# Steckkarte.net
KiCad netlist of a schematic drawn in EAGLE
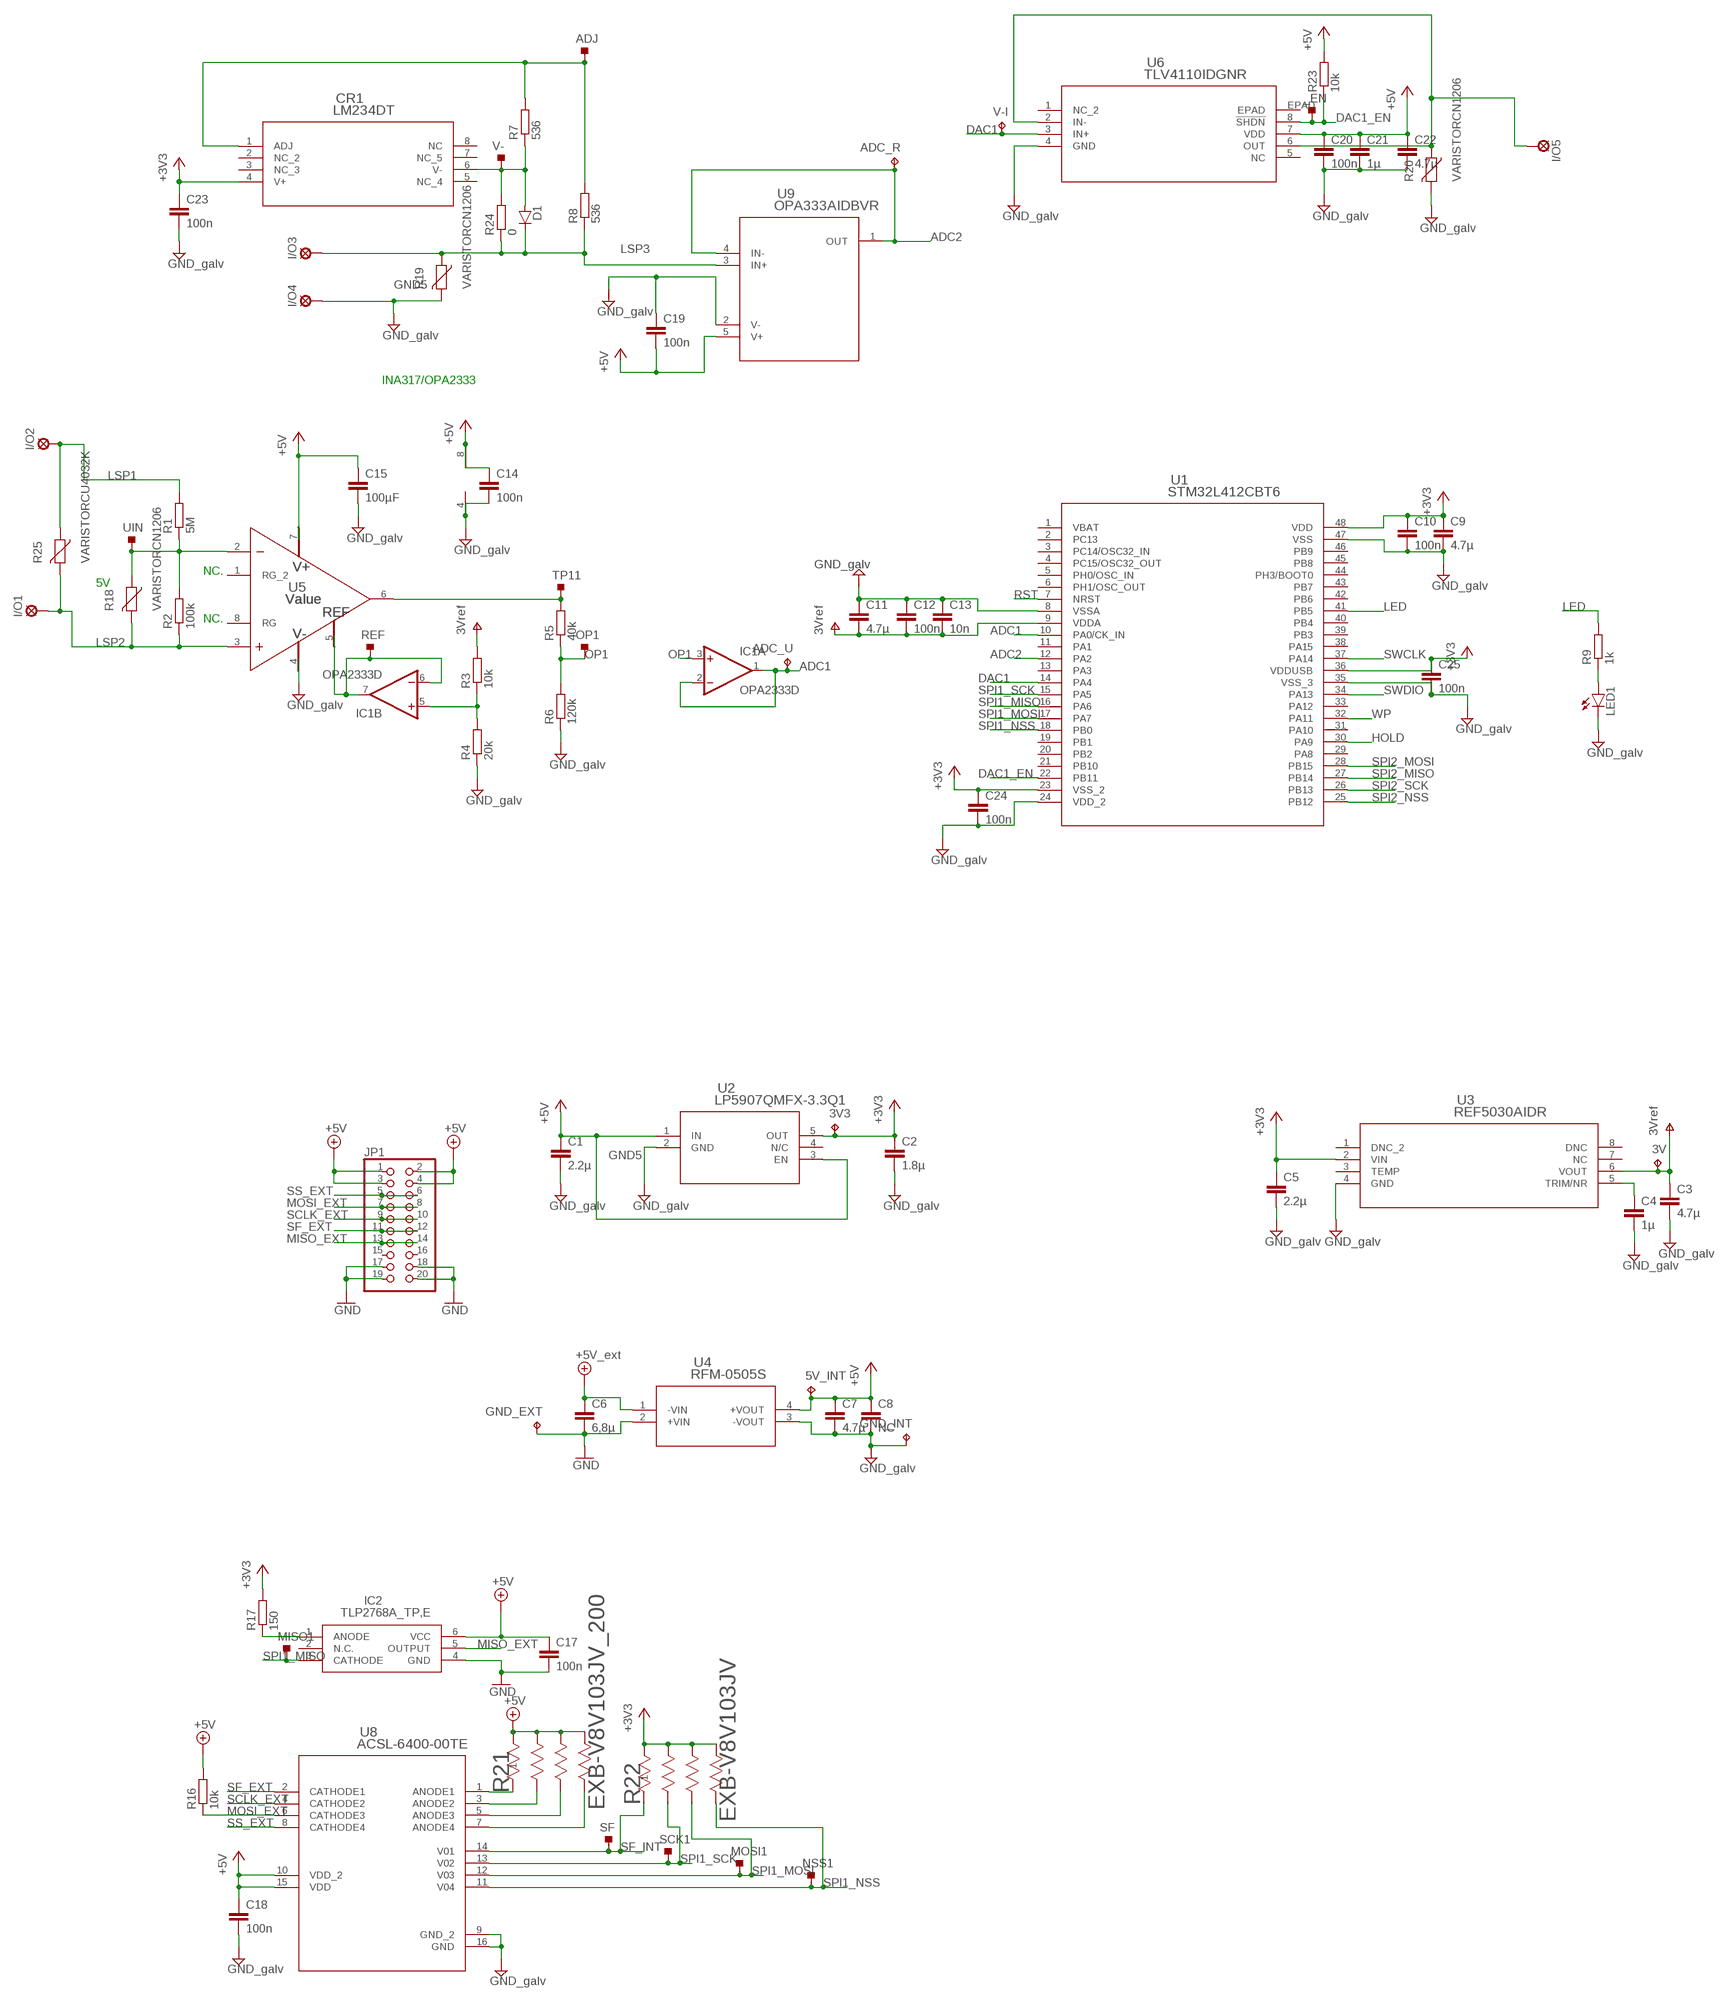
[diagram p0: schematic, sheet 1, part 1 of 2]
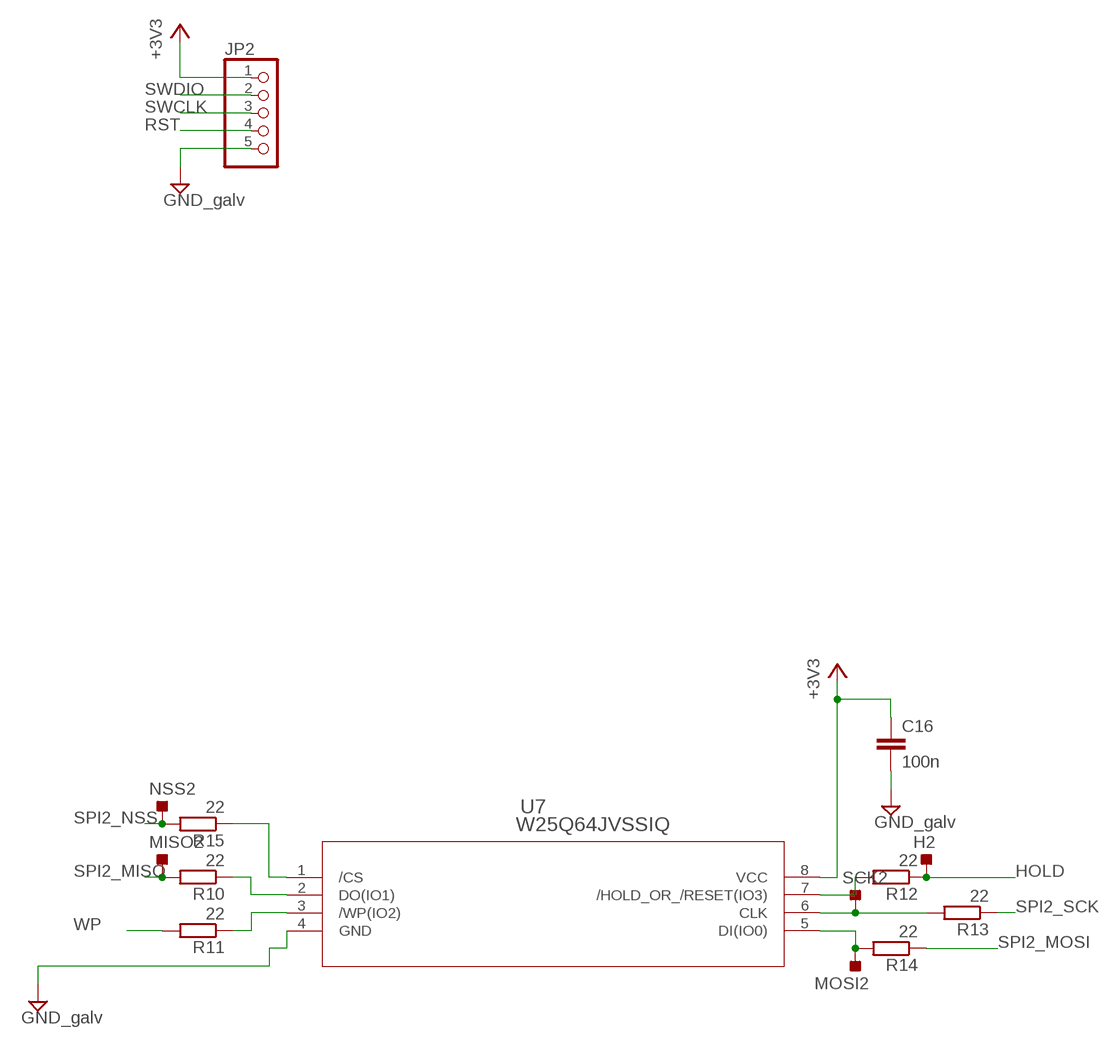
[diagram p1: schematic, sheet 1, part 2 of 2]

(export (version "E")
  (design (tool "Eeschema 10.0.6"))
  (components
    (comp (ref "3V")
      (value "TPPAD1-13")
      (footprint "eagle-import:P1-13")
      (libsource (lib "eagle-import") (part "TPPAD1-13"))
    )
    (comp (ref "3V3")
      (value "TPPAD1-13")
      (footprint "eagle-import:P1-13")
      (libsource (lib "eagle-import") (part "TPPAD1-13"))
    )
    (comp (ref "5V_INT")
      (value "TPPAD1-13")
      (footprint "eagle-import:P1-13")
      (libsource (lib "eagle-import") (part "TPPAD1-13"))
    )
    (comp (ref "ADC_R")
      (value "TPPAD1-13")
      (footprint "eagle-import:P1-13")
      (libsource (lib "eagle-import") (part "TPPAD1-13"))
    )
    (comp (ref "ADC_U")
      (value "TPPAD1-13")
      (footprint "eagle-import:P1-13")
      (libsource (lib "eagle-import") (part "TPPAD1-13"))
    )
    (comp (ref "ADJ")
      (value "TESTPOINT_TPS-SMD-10SN")
      (footprint "eagle-import:TESTPOINT_SMD-10SN")
      (libsource (lib "eagle-import") (part "TESTPOINT_TPS-SMD-10SN"))
    )
    (comp (ref "C1")
      (value "2.2µ")
      (footprint "eagle-import:C0603K")
      (libsource (lib "eagle-import") (part "C-EUC0603K"))
    )
    (comp (ref "C2")
      (value "1.8µ")
      (footprint "eagle-import:C1206K")
      (libsource (lib "eagle-import") (part "C-EUC1206K"))
    )
    (comp (ref "C3")
      (value "4.7µ")
      (footprint "eagle-import:C0603K")
      (libsource (lib "eagle-import") (part "C-EUC0603K"))
    )
    (comp (ref "C4")
      (value "1µ")
      (footprint "eagle-import:C0603K")
      (libsource (lib "eagle-import") (part "C-EUC0603K"))
    )
    (comp (ref "C5")
      (value "2.2µ")
      (footprint "eagle-import:C0603K")
      (libsource (lib "eagle-import") (part "C-EUC0603K"))
    )
    (comp (ref "C6")
      (value "6,8µ")
      (footprint "eagle-import:C0603K")
      (libsource (lib "eagle-import") (part "resistor_348_C-EUC0603K"))
    )
    (comp (ref "C7")
      (value "4.7µ")
      (footprint "eagle-import:C0603K")
      (libsource (lib "eagle-import") (part "resistor_348_C-EUC0603K"))
    )
    (comp (ref "C8")
      (value "NC")
      (footprint "eagle-import:C0603K")
      (libsource (lib "eagle-import") (part "resistor_348_C-EUC0603K"))
    )
    (comp (ref "C9")
      (value "4.7µ")
      (footprint "eagle-import:C0603K")
      (libsource (lib "eagle-import") (part "C-EUC0603K"))
    )
    (comp (ref "C10")
      (value "100n")
      (footprint "eagle-import:C0603K")
      (libsource (lib "eagle-import") (part "C-EUC0603K"))
    )
    (comp (ref "C11")
      (value "4.7µ")
      (footprint "eagle-import:C0603K")
      (libsource (lib "eagle-import") (part "C-EUC0603K"))
    )
    (comp (ref "C12")
      (value "100n")
      (footprint "eagle-import:C0603K")
      (libsource (lib "eagle-import") (part "C-EUC0603K"))
    )
    (comp (ref "C13")
      (value "10n")
      (footprint "eagle-import:C0603K")
      (libsource (lib "eagle-import") (part "C-EUC0603K"))
    )
    (comp (ref "C14")
      (value "100n")
      (footprint "eagle-import:C0603K")
      (libsource (lib "eagle-import") (part "C-EUC0603K"))
    )
    (comp (ref "C15")
      (value "100µF")
      (footprint "eagle-import:C1206K")
      (libsource (lib "eagle-import") (part "resistor_348_C-EUC1206K"))
    )
    (comp (ref "C16")
      (value "100n")
      (footprint "eagle-import:C0603K")
      (libsource (lib "eagle-import") (part "C-EUC0603K"))
    )
    (comp (ref "C17")
      (value "100n")
      (footprint "eagle-import:C0603K")
      (libsource (lib "eagle-import") (part "C-EUC0603K"))
    )
    (comp (ref "C18")
      (value "100n")
      (footprint "eagle-import:C0603K")
      (libsource (lib "eagle-import") (part "C-EUC0603K"))
    )
    (comp (ref "C19")
      (value "100n")
      (footprint "eagle-import:C0603K")
      (libsource (lib "eagle-import") (part "C-EUC0603K"))
    )
    (comp (ref "C20")
      (value "100n")
      (footprint "eagle-import:C0603K")
      (libsource (lib "eagle-import") (part "C-EUC0603K"))
    )
    (comp (ref "C21")
      (value "1µ")
      (footprint "eagle-import:C0603K")
      (libsource (lib "eagle-import") (part "C-EUC0603K"))
    )
    (comp (ref "C22")
      (value "4.7µ")
      (footprint "eagle-import:C0603K")
      (libsource (lib "eagle-import") (part "C-EUC0603K"))
    )
    (comp (ref "C23")
      (value "100n")
      (footprint "eagle-import:C0603K")
      (libsource (lib "eagle-import") (part "C-EUC0603K"))
    )
    (comp (ref "C24")
      (value "100n")
      (footprint "eagle-import:C0603K")
      (libsource (lib "eagle-import") (part "C-EUC0603K"))
    )
    (comp (ref "C25")
      (value "100n")
      (footprint "eagle-import:C0603K")
      (libsource (lib "eagle-import") (part "C-EUC0603K"))
    )
    (comp (ref "CR1")
      (value "LM234DT")
      (footprint "eagle-import:SO-8")
      (libsource (lib "eagle-import") (part "LM234DT"))
    )
    (comp (ref "D1")
      (value "D-SOD123")
      (footprint "eagle-import:SOD123")
      (libsource (lib "eagle-import") (part "D-SOD123"))
    )
    (comp (ref "GND_EXT")
      (value "TPPAD1-13")
      (footprint "eagle-import:P1-13")
      (libsource (lib "eagle-import") (part "TPPAD1-13"))
    )
    (comp (ref "GND_INT")
      (value "TPPAD1-13")
      (footprint "eagle-import:P1-13")
      (libsource (lib "eagle-import") (part "TPPAD1-13"))
    )
    (comp (ref "H2")
      (value "TESTPOINT_TPS-SMD-10SN")
      (footprint "eagle-import:TESTPOINT_SMD-10SN")
      (libsource (lib "eagle-import") (part "TESTPOINT_TPS-SMD-10SN"))
    )
    (comp (ref "I/O1")
      (value "SE14")
      (footprint "eagle-import:SE14")
      (libsource (lib "eagle-import") (part "SE14"))
    )
    (comp (ref "I/O2")
      (value "SE14")
      (footprint "eagle-import:SE14")
      (libsource (lib "eagle-import") (part "SE14"))
    )
    (comp (ref "I/O3")
      (value "SE14")
      (footprint "eagle-import:SE14")
      (libsource (lib "eagle-import") (part "SE14"))
    )
    (comp (ref "I/O4")
      (value "SE14")
      (footprint "eagle-import:SE14")
      (libsource (lib "eagle-import") (part "SE14"))
    )
    (comp (ref "I/O5")
      (value "SE14")
      (footprint "eagle-import:SE14")
      (libsource (lib "eagle-import") (part "SE14"))
    )
    (comp (ref "IC1")
      (value "OPA2333D")
      (footprint "eagle-import:SO08")
      (libsource (lib "eagle-import") (part "OPA2333D"))
    )
    (comp (ref "IC2")
      (value "TLP2768A_TP,E")
      (footprint "eagle-import:SOIC127P1000X220-6N")
      (fields
        (field (name "MANUFACTURER_PART_NUMBER") "TLP2768A(TP,E")
        (field (name "MOUSER_PART_NUMBER") "757-TLP2768ATPE")
      )
      (libsource (lib "eagle-import") (part "TLP2768A_TP,E"))
    )
    (comp (ref "JP1")
      (value "PINHD-2X10/90")
      (footprint "eagle-import:2X10_90")
      (libsource (lib "eagle-import") (part "PINHD-2X10/90"))
    )
    (comp (ref "JP2")
      (value "PINHD-1X5")
      (footprint "eagle-import:1X05")
      (libsource (lib "eagle-import") (part "PINHD-1X5"))
    )
    (comp (ref "LED1")
      (value "LED5MM")
      (footprint "eagle-import:LED5MM")
      (libsource (lib "eagle-import") (part "LED5MM"))
    )
    (comp (ref "MISO1")
      (value "TESTPOINT_TPS-SMD-10SN")
      (footprint "eagle-import:TESTPOINT_SMD-10SN")
      (libsource (lib "eagle-import") (part "TESTPOINT_TPS-SMD-10SN"))
    )
    (comp (ref "MISO2")
      (value "TESTPOINT_TPS-SMD-10SN")
      (footprint "eagle-import:TESTPOINT_SMD-10SN")
      (libsource (lib "eagle-import") (part "TESTPOINT_TPS-SMD-10SN"))
    )
    (comp (ref "MOSI1")
      (value "TESTPOINT_TPS-SMD-10SN")
      (footprint "eagle-import:TESTPOINT_SMD-10SN")
      (libsource (lib "eagle-import") (part "TESTPOINT_TPS-SMD-10SN"))
    )
    (comp (ref "MOSI2")
      (value "TESTPOINT_TPS-SMD-10SN")
      (footprint "eagle-import:TESTPOINT_SMD-10SN")
      (libsource (lib "eagle-import") (part "TESTPOINT_TPS-SMD-10SN"))
    )
    (comp (ref "NSS1")
      (value "TESTPOINT_TPS-SMD-10SN")
      (footprint "eagle-import:TESTPOINT_SMD-10SN")
      (libsource (lib "eagle-import") (part "TESTPOINT_TPS-SMD-10SN"))
    )
    (comp (ref "NSS2")
      (value "TESTPOINT_TPS-SMD-10SN")
      (footprint "eagle-import:TESTPOINT_SMD-10SN")
      (libsource (lib "eagle-import") (part "TESTPOINT_TPS-SMD-10SN"))
    )
    (comp (ref "OP1")
      (value "TESTPOINT_TPS-SMD-10SN")
      (footprint "eagle-import:TESTPOINT_SMD-10SN")
      (libsource (lib "eagle-import") (part "TESTPOINT_TPS-SMD-10SN"))
    )
    (comp (ref "R1")
      (value "5M")
      (footprint "eagle-import:R1206")
      (libsource (lib "eagle-import") (part "R-EU_R1206"))
    )
    (comp (ref "R2")
      (value "100k")
      (footprint "eagle-import:R1206")
      (libsource (lib "eagle-import") (part "R-EU_R1206"))
    )
    (comp (ref "R3")
      (value "10k")
      (footprint "eagle-import:R0603")
      (libsource (lib "eagle-import") (part "R-EU_R0603"))
    )
    (comp (ref "R4")
      (value "20k")
      (footprint "eagle-import:R0603")
      (libsource (lib "eagle-import") (part "R-EU_R0603"))
    )
    (comp (ref "R5")
      (value "40k")
      (footprint "eagle-import:R0603")
      (libsource (lib "eagle-import") (part "R-EU_R0603"))
    )
    (comp (ref "R6")
      (value "120k")
      (footprint "eagle-import:R0603")
      (libsource (lib "eagle-import") (part "R-EU_R0603"))
    )
    (comp (ref "R7")
      (value "536")
      (footprint "eagle-import:R0603")
      (libsource (lib "eagle-import") (part "R-EU_R0603"))
    )
    (comp (ref "R8")
      (value "536")
      (footprint "eagle-import:R0603")
      (libsource (lib "eagle-import") (part "R-EU_R0603"))
    )
    (comp (ref "R9")
      (value "1k")
      (footprint "eagle-import:R0603")
      (libsource (lib "eagle-import") (part "R-EU_R0603"))
    )
    (comp (ref "R10")
      (value "22")
      (footprint "eagle-import:R0603")
      (libsource (lib "eagle-import") (part "R-EU_R0603"))
    )
    (comp (ref "R11")
      (value "22")
      (footprint "eagle-import:R0603")
      (libsource (lib "eagle-import") (part "R-EU_R0603"))
    )
    (comp (ref "R12")
      (value "22")
      (footprint "eagle-import:R0603")
      (libsource (lib "eagle-import") (part "R-EU_R0603"))
    )
    (comp (ref "R13")
      (value "22")
      (footprint "eagle-import:R0603")
      (libsource (lib "eagle-import") (part "R-EU_R0603"))
    )
    (comp (ref "R14")
      (value "22")
      (footprint "eagle-import:R0603")
      (libsource (lib "eagle-import") (part "R-EU_R0603"))
    )
    (comp (ref "R15")
      (value "22")
      (footprint "eagle-import:R0603")
      (libsource (lib "eagle-import") (part "R-EU_R0603"))
    )
    (comp (ref "R16")
      (value "10k")
      (footprint "eagle-import:R0603")
      (libsource (lib "eagle-import") (part "R-EU_R0603"))
    )
    (comp (ref "R17")
      (value "150")
      (footprint "eagle-import:R0603")
      (libsource (lib "eagle-import") (part "R-EU_R0603"))
    )
    (comp (ref "R18")
      (value "VARISTORCN1206")
      (footprint "eagle-import:CT_CN1206")
      (libsource (lib "eagle-import") (part "VARISTORCN1206"))
    )
    (comp (ref "R19")
      (value "VARISTORCN1206")
      (footprint "eagle-import:CT_CN1206")
      (libsource (lib "eagle-import") (part "VARISTORCN1206"))
    )
    (comp (ref "R20")
      (value "VARISTORCN1206")
      (footprint "eagle-import:CT_CN1206")
      (libsource (lib "eagle-import") (part "VARISTORCN1206"))
    )
    (comp (ref "R21")
      (value "EXB-V8V103JV_200")
      (footprint "eagle-import:EXBV8V")
      (fields (field (name "MANUFACTURER_PART_NUMBER") "EXB-V8V103JV"))
      (libsource (lib "eagle-import") (part "EXB-V8V103JV"))
    )
    (comp (ref "R22")
      (value "EXB-V8V103JV")
      (footprint "eagle-import:EXBV8V")
      (libsource (lib "eagle-import") (part "EXB-V8V103JV"))
    )
    (comp (ref "R23")
      (value "10k")
      (footprint "eagle-import:R0603")
      (libsource (lib "eagle-import") (part "R-EU_R0603"))
    )
    (comp (ref "R24")
      (value "0")
      (footprint "eagle-import:R0603")
      (libsource (lib "eagle-import") (part "R-EU_R0603"))
    )
    (comp (ref "R25")
      (value "VARISTORCU4032K")
      (footprint "eagle-import:CU4032K")
      (libsource (lib "eagle-import") (part "VARISTORCU4032K"))
    )
    (comp (ref "REF")
      (value "TESTPOINT_TPS-SMD-10SN")
      (footprint "eagle-import:TESTPOINT_SMD-10SN")
      (libsource (lib "eagle-import") (part "TESTPOINT_TPS-SMD-10SN"))
    )
    (comp (ref "SCK1")
      (value "TESTPOINT_TPS-SMD-10SN")
      (footprint "eagle-import:TESTPOINT_SMD-10SN")
      (libsource (lib "eagle-import") (part "TESTPOINT_TPS-SMD-10SN"))
    )
    (comp (ref "SCK2")
      (value "TESTPOINT_TPS-SMD-10SN")
      (footprint "eagle-import:TESTPOINT_SMD-10SN")
      (libsource (lib "eagle-import") (part "TESTPOINT_TPS-SMD-10SN"))
    )
    (comp (ref "SF")
      (value "TESTPOINT_TPS-SMD-10SN")
      (footprint "eagle-import:TESTPOINT_SMD-10SN")
      (libsource (lib "eagle-import") (part "TESTPOINT_TPS-SMD-10SN"))
    )
    (comp (ref "TP11")
      (value "TESTPOINT_TPS-SMD-10SN")
      (footprint "eagle-import:TESTPOINT_SMD-10SN")
      (libsource (lib "eagle-import") (part "TESTPOINT_TPS-SMD-10SN"))
    )
    (comp (ref "U1")
      (value "STM32L412CBT6")
      (footprint "eagle-import:LQFP-48")
      (fields (field (name "COPYRIGHT") "Copyright (C) 2018 Accelerated Designs. All rights reserved"))
      (libsource (lib "eagle-import") (part "STM32L412CBT6"))
    )
    (comp (ref "U2")
      (value "LP5907QMFX-3.3Q1")
      (footprint "eagle-import:DBV5")
      (libsource (lib "eagle-import") (part "LP5907QMFX-3.3Q1"))
    )
    (comp (ref "U3")
      (value "REF5030AIDR")
      (footprint "eagle-import:D8")
      (libsource (lib "eagle-import") (part "REF5030AIDR"))
    )
    (comp (ref "U4")
      (value "RFM-0505S")
      (footprint "eagle-import:RFM-0505S")
      (fields (field (name "COPYRIGHT") "Copyright (C) 2018 Accelerated Designs. All rights reserved"))
      (libsource (lib "eagle-import") (part "RFM-0505S"))
    )
    (comp (ref "U5")
      (value "Value")
      (footprint "eagle-import:DGK0008A_N")
      (fields (field (name "MANUFACTURER") "Texas Instruments") (field (name "PARTNUMBER") "INA317IDGKR"))
      (libsource (lib "eagle-import") (part "INA317IDGKR"))
    )
    (comp (ref "U6")
      (value "TLV4110IDGNR")
      (footprint "eagle-import:DGN8_1P89X1P57")
      (fields
        (field (name "GENERIC_PART_NUMBER") "TLV4110")
        (field (name "MANUFACTURER") "Texas Instruments")
      )
      (libsource (lib "eagle-import") (part "TLV4110IDGNR"))
    )
    (comp (ref "U7")
      (value "W25Q64JVSSIQ")
      (footprint "eagle-import:SOIC-8_5P28X5P28")
      (fields (field (name "COPYRIGHT") "Copyright (C) 2018 Accelerated Designs. All rights reserved"))
      (libsource (lib "eagle-import") (part "W25Q64JVSSIQ"))
    )
    (comp (ref "U8")
      (value "ACSL-6400-00TE")
      (footprint "eagle-import:SOIC_6400-00TE")
      (fields (field (name "COPYRIGHT") "Copyright (C) 2018 Accelerated Designs. All rights reserved"))
      (libsource (lib "eagle-import") (part "ACSL-6400-00TE"))
    )
    (comp (ref "U9")
      (value "OPA333AIDBVR")
      (footprint "eagle-import:DBV5")
      (fields (field (name "GENERIC_PART_NUMBER") "OPA333") (field (name "MANUFACTURER") "Texas Instruments"))
      (libsource (lib "eagle-import") (part "OPA333AIDBVR"))
    )
    (comp (ref "UIN")
      (value "TESTPOINT_TPS-SMD-10SN")
      (footprint "eagle-import:TESTPOINT_SMD-10SN")
      (libsource (lib "eagle-import") (part "TESTPOINT_TPS-SMD-10SN"))
    )
    (comp (ref "V-")
      (value "TESTPOINT_TPS-SMD-10SN")
      (footprint "eagle-import:TESTPOINT_SMD-10SN")
      (libsource (lib "eagle-import") (part "TESTPOINT_TPS-SMD-10SN"))
    )
    (comp (ref "V-I")
      (value "TPPAD1-13")
      (footprint "eagle-import:P1-13")
      (libsource (lib "eagle-import") (part "TPPAD1-13"))
    )
    (comp (ref "_EN")
      (value "TESTPOINT_TPS-SMD-10SN")
      (footprint "eagle-import:TESTPOINT_SMD-10SN")
      (libsource (lib "eagle-import") (part "TESTPOINT_TPS-SMD-10SN"))
    )
  )
  (nets
    (net (code "1") (name "+3V3") (class "Default")
      (node (ref "3V3") (pin "TP") (pinfunction "TP_TP") (pintype "input"))
      (node (ref "C10") (pin "1") (pinfunction "1_1") (pintype "passive"))
      (node (ref "C16") (pin "1") (pinfunction "1_1") (pintype "passive"))
      (node (ref "C2") (pin "1") (pinfunction "1_1") (pintype "passive"))
      (node (ref "C23") (pin "1") (pinfunction "1_1") (pintype "passive"))
      (node (ref "C24") (pin "1") (pinfunction "1_1") (pintype "passive"))
      (node (ref "C25") (pin "1") (pinfunction "1_1") (pintype "passive"))
      (node (ref "C5") (pin "1") (pinfunction "1_1") (pintype "passive"))
      (node (ref "C9") (pin "1") (pinfunction "1_1") (pintype "passive"))
      (node (ref "CR1") (pin "4") (pinfunction "V+_4") (pintype "power_in"))
      (node (ref "JP2") (pin "1") (pinfunction "1_1") (pintype "passive"))
      (node (ref "R17") (pin "2") (pinfunction "2_2") (pintype "passive"))
      (node (ref "R22") (pin "5") (pinfunction "5_5") (pintype "passive"))
      (node (ref "R22") (pin "6") (pinfunction "6_6") (pintype "passive"))
      (node (ref "R22") (pin "7") (pinfunction "7_7") (pintype "passive"))
      (node (ref "R22") (pin "8") (pinfunction "8_8") (pintype "passive"))
      (node (ref "U1") (pin "23") (pinfunction "VSS_2_23") (pintype "power_in"))
      (node (ref "U1") (pin "36") (pinfunction "VDDUSB_36") (pintype "power_in"))
      (node (ref "U1") (pin "48") (pinfunction "VDD_48") (pintype "power_in"))
      (node (ref "U2") (pin "5") (pinfunction "OUT_5") (pintype "output"))
      (node (ref "U3") (pin "2") (pinfunction "VIN_2") (pintype "input"))
      (node (ref "U7") (pin "8") (pinfunction "VCC_8") (pintype "power_in"))
    )
    (net (code "2") (name "+5V") (class "Default")
      (node (ref "5V_INT") (pin "TP") (pinfunction "TP_TP") (pintype "input"))
      (node (ref "C1") (pin "1") (pinfunction "1_1") (pintype "passive"))
      (node (ref "C14") (pin "1") (pinfunction "1_1") (pintype "passive"))
      (node (ref "C15") (pin "1") (pinfunction "1_1") (pintype "passive"))
      (node (ref "C17") (pin "1") (pinfunction "1_1") (pintype "passive"))
      (node (ref "C18") (pin "1") (pinfunction "1_1") (pintype "passive"))
      (node (ref "C19") (pin "2") (pinfunction "2_2") (pintype "passive"))
      (node (ref "C20") (pin "1") (pinfunction "1_1") (pintype "passive"))
      (node (ref "C21") (pin "1") (pinfunction "1_1") (pintype "passive"))
      (node (ref "C22") (pin "1") (pinfunction "1_1") (pintype "passive"))
      (node (ref "C6") (pin "1") (pinfunction "1_1") (pintype "passive"))
      (node (ref "C7") (pin "1") (pinfunction "1_1") (pintype "passive"))
      (node (ref "C8") (pin "1") (pinfunction "1_1") (pintype "passive"))
      (node (ref "IC1") (pin "8") (pinfunction "V+_8") (pintype "power_in"))
      (node (ref "IC2") (pin "6") (pinfunction "VCC_6") (pintype "bidirectional"))
      (node (ref "JP1") (pin "1") (pinfunction "1_1") (pintype "passive"))
      (node (ref "JP1") (pin "2") (pinfunction "2_2") (pintype "passive"))
      (node (ref "JP1") (pin "3") (pinfunction "3_3") (pintype "passive"))
      (node (ref "JP1") (pin "4") (pinfunction "4_4") (pintype "passive"))
      (node (ref "R16") (pin "2") (pinfunction "2_2") (pintype "passive"))
      (node (ref "R21") (pin "5") (pinfunction "5_5") (pintype "passive"))
      (node (ref "R21") (pin "6") (pinfunction "6_6") (pintype "passive"))
      (node (ref "R21") (pin "7") (pinfunction "7_7") (pintype "passive"))
      (node (ref "R21") (pin "8") (pinfunction "8_8") (pintype "passive"))
      (node (ref "R23") (pin "2") (pinfunction "2_2") (pintype "passive"))
      (node (ref "U2") (pin "1") (pinfunction "IN_1") (pintype "input"))
      (node (ref "U2") (pin "3") (pinfunction "EN_3") (pintype "input"))
      (node (ref "U4") (pin "1") (pinfunction "-VIN_1") (pintype "input"))
      (node (ref "U4") (pin "4") (pinfunction "+VOUT_4") (pintype "output"))
      (node (ref "U5") (pin "7") (pinfunction "V+_7") (pintype "power_in"))
      (node (ref "U6") (pin "7") (pinfunction "VDD_7") (pintype "power_in"))
      (node (ref "U8") (pin "10") (pinfunction "VDD_2_10") (pintype "power_in"))
      (node (ref "U8") (pin "15") (pinfunction "VDD_15") (pintype "power_in"))
      (node (ref "U9") (pin "5") (pinfunction "V+_5") (pintype "power_in"))
    )
    (net (code "3") (name "/ADC1") (class "Default")
      (node (ref "ADC_U") (pin "TP") (pinfunction "TP_TP") (pintype "input"))
      (node (ref "IC1") (pin "1") (pinfunction "OUT_1") (pintype "output"))
      (node (ref "IC1") (pin "2") (pinfunction "-IN_2") (pintype "input"))
      (node (ref "U1") (pin "10") (pinfunction "PA0/CK_IN_10") (pintype "bidirectional"))
    )
    (net (code "4") (name "/ADC2") (class "Default")
      (node (ref "ADC_R") (pin "TP") (pinfunction "TP_TP") (pintype "input"))
      (node (ref "U1") (pin "12") (pinfunction "PA2_12") (pintype "bidirectional"))
      (node (ref "U9") (pin "1") (pinfunction "OUT_1") (pintype "output"))
      (node (ref "U9") (pin "4") (pinfunction "IN-_4") (pintype "input"))
    )
    (net (code "5") (name "/DAC1") (class "Default")
      (node (ref "U1") (pin "14") (pinfunction "PA4_14") (pintype "bidirectional"))
      (node (ref "U6") (pin "3") (pinfunction "IN+_3") (pintype "input"))
      (node (ref "V-I") (pin "TP") (pinfunction "TP_TP") (pintype "input"))
    )
    (net (code "6") (name "/DAC1_EN") (class "Default")
      (node (ref "R23") (pin "1") (pinfunction "1_1") (pintype "passive"))
      (node (ref "U1") (pin "22") (pinfunction "PB11_22") (pintype "bidirectional"))
      (node (ref "U6") (pin "8") (pinfunction "~{SHDN}_8") (pintype "passive"))
      (node (ref "_EN") (pin "TP") (pinfunction "TP_TP") (pintype "passive"))
    )
    (net (code "7") (name "/HOLD") (class "Default")
      (node (ref "H2") (pin "TP") (pinfunction "TP_TP") (pintype "passive"))
      (node (ref "R12") (pin "1") (pinfunction "1_1") (pintype "passive"))
      (node (ref "U1") (pin "30") (pinfunction "PA9_30") (pintype "bidirectional"))
    )
    (net (code "8") (name "/LED") (class "Default")
      (node (ref "R9") (pin "2") (pinfunction "2_2") (pintype "passive"))
      (node (ref "U1") (pin "41") (pinfunction "PB5_41") (pintype "bidirectional"))
    )
    (net (code "9") (name "/LSP1") (class "Default")
      (node (ref "I/O2") (pin "MP") (pinfunction "MP_MP") (pintype "passive"))
      (node (ref "R1") (pin "2") (pinfunction "2_2") (pintype "passive"))
      (node (ref "R25") (pin "1") (pinfunction "1_1") (pintype "passive"))
    )
    (net (code "10") (name "/LSP2") (class "Default")
      (node (ref "I/O1") (pin "MP") (pinfunction "MP_MP") (pintype "passive"))
      (node (ref "R18") (pin "2") (pinfunction "2_2") (pintype "passive"))
      (node (ref "R2") (pin "1") (pinfunction "1_1") (pintype "passive"))
      (node (ref "R25") (pin "2") (pinfunction "2_2") (pintype "passive"))
      (node (ref "U5") (pin "3") (pinfunction "IN+_3") (pintype "input"))
    )
    (net (code "11") (name "/LSP3") (class "Default")
      (node (ref "D1") (pin "1") (pinfunction "C_1") (pintype "passive"))
      (node (ref "I/O3") (pin "MP") (pinfunction "MP_MP") (pintype "passive"))
      (node (ref "R19") (pin "1") (pinfunction "1_1") (pintype "passive"))
      (node (ref "R24") (pin "1") (pinfunction "1_1") (pintype "passive"))
      (node (ref "R8") (pin "1") (pinfunction "1_1") (pintype "passive"))
      (node (ref "U9") (pin "3") (pinfunction "IN+_3") (pintype "input"))
    )
    (net (code "12") (name "/MISO_EXT") (class "Default")
      (node (ref "IC2") (pin "5") (pinfunction "OUTPUT_5") (pintype "bidirectional"))
      (node (ref "JP1") (pin "13") (pinfunction "13_13") (pintype "passive"))
      (node (ref "JP1") (pin "14") (pinfunction "14_14") (pintype "passive"))
    )
    (net (code "13") (name "/MOSI_EXT") (class "Default")
      (node (ref "JP1") (pin "7") (pinfunction "7_7") (pintype "passive"))
      (node (ref "JP1") (pin "8") (pinfunction "8_8") (pintype "passive"))
      (node (ref "R16") (pin "1") (pinfunction "1_1") (pintype "passive"))
      (node (ref "U8") (pin "6") (pinfunction "CATHODE3_6") (pintype "bidirectional"))
    )
    (net (code "14") (name "/OP1") (class "Default")
      (node (ref "IC1") (pin "3") (pinfunction "+IN_3") (pintype "input"))
      (node (ref "OP1") (pin "TP") (pinfunction "TP_TP") (pintype "passive"))
      (node (ref "R5") (pin "1") (pinfunction "1_1") (pintype "passive"))
      (node (ref "R6") (pin "2") (pinfunction "2_2") (pintype "passive"))
    )
    (net (code "15") (name "/RST") (class "Default")
      (node (ref "JP2") (pin "4") (pinfunction "4_4") (pintype "passive"))
      (node (ref "U1") (pin "7") (pinfunction "NRST_7") (pintype "bidirectional"))
    )
    (net (code "16") (name "/SCLK_EXT") (class "Default")
      (node (ref "JP1") (pin "10") (pinfunction "10_10") (pintype "passive"))
      (node (ref "JP1") (pin "9") (pinfunction "9_9") (pintype "passive"))
      (node (ref "U8") (pin "4") (pinfunction "CATHODE2_4") (pintype "bidirectional"))
    )
    (net (code "17") (name "/SF_EXT") (class "Default")
      (node (ref "JP1") (pin "11") (pinfunction "11_11") (pintype "passive"))
      (node (ref "JP1") (pin "12") (pinfunction "12_12") (pintype "passive"))
      (node (ref "U8") (pin "2") (pinfunction "CATHODE1_2") (pintype "bidirectional"))
    )
    (net (code "18") (name "/SF_INT") (class "Default")
      (node (ref "R22") (pin "1") (pinfunction "1_1") (pintype "passive"))
      (node (ref "SF") (pin "TP") (pinfunction "TP_TP") (pintype "passive"))
      (node (ref "U8") (pin "14") (pinfunction "V01_14") (pintype "bidirectional"))
    )
    (net (code "19") (name "/SPI1_MISO") (class "Default")
      (node (ref "IC2") (pin "3") (pinfunction "CATHODE_3") (pintype "bidirectional"))
      (node (ref "MISO1") (pin "TP") (pinfunction "TP_TP") (pintype "passive"))
      (node (ref "U1") (pin "16") (pinfunction "PA6_16") (pintype "bidirectional"))
    )
    (net (code "20") (name "/SPI1_MOSI") (class "Default")
      (node (ref "MOSI1") (pin "TP") (pinfunction "TP_TP") (pintype "passive"))
      (node (ref "R22") (pin "3") (pinfunction "3_3") (pintype "passive"))
      (node (ref "U1") (pin "17") (pinfunction "PA7_17") (pintype "bidirectional"))
      (node (ref "U8") (pin "12") (pinfunction "V03_12") (pintype "bidirectional"))
    )
    (net (code "21") (name "/SPI1_NSS") (class "Default")
      (node (ref "NSS1") (pin "TP") (pinfunction "TP_TP") (pintype "passive"))
      (node (ref "R22") (pin "4") (pinfunction "4_4") (pintype "passive"))
      (node (ref "U1") (pin "18") (pinfunction "PB0_18") (pintype "bidirectional"))
      (node (ref "U8") (pin "11") (pinfunction "V04_11") (pintype "bidirectional"))
    )
    (net (code "22") (name "/SPI1_SCK") (class "Default")
      (node (ref "R22") (pin "2") (pinfunction "2_2") (pintype "passive"))
      (node (ref "SCK1") (pin "TP") (pinfunction "TP_TP") (pintype "passive"))
      (node (ref "U1") (pin "15") (pinfunction "PA5_15") (pintype "bidirectional"))
      (node (ref "U8") (pin "13") (pinfunction "V02_13") (pintype "bidirectional"))
    )
    (net (code "23") (name "/SPI2_MISO") (class "Default")
      (node (ref "MISO2") (pin "TP") (pinfunction "TP_TP") (pintype "passive"))
      (node (ref "R10") (pin "2") (pinfunction "2_2") (pintype "passive"))
      (node (ref "U1") (pin "27") (pinfunction "PB14_27") (pintype "bidirectional"))
    )
    (net (code "24") (name "/SPI2_MOSI") (class "Default")
      (node (ref "R14") (pin "1") (pinfunction "1_1") (pintype "passive"))
      (node (ref "U1") (pin "28") (pinfunction "PB15_28") (pintype "bidirectional"))
    )
    (net (code "25") (name "/SPI2_NSS") (class "Default")
      (node (ref "NSS2") (pin "TP") (pinfunction "TP_TP") (pintype "passive"))
      (node (ref "R15") (pin "2") (pinfunction "2_2") (pintype "passive"))
      (node (ref "U1") (pin "25") (pinfunction "PB12_25") (pintype "bidirectional"))
    )
    (net (code "26") (name "/SPI2_SCK") (class "Default")
      (node (ref "R13") (pin "1") (pinfunction "1_1") (pintype "passive"))
      (node (ref "U1") (pin "26") (pinfunction "PB13_26") (pintype "bidirectional"))
    )
    (net (code "27") (name "/SS_EXT") (class "Default")
      (node (ref "JP1") (pin "5") (pinfunction "5_5") (pintype "passive"))
      (node (ref "JP1") (pin "6") (pinfunction "6_6") (pintype "passive"))
      (node (ref "U8") (pin "8") (pinfunction "CATHODE4_8") (pintype "bidirectional"))
    )
    (net (code "28") (name "/SWCLK") (class "Default")
      (node (ref "JP2") (pin "3") (pinfunction "3_3") (pintype "passive"))
      (node (ref "U1") (pin "37") (pinfunction "PA14_37") (pintype "bidirectional"))
    )
    (net (code "29") (name "/SWDIO") (class "Default")
      (node (ref "JP2") (pin "2") (pinfunction "2_2") (pintype "passive"))
      (node (ref "U1") (pin "34") (pinfunction "PA13_34") (pintype "bidirectional"))
    )
    (net (code "30") (name "/VBAT") (class "Default")
      (node (ref "U1") (pin "1") (pinfunction "VBAT_1") (pintype "power_in"))
    )
    (net (code "31") (name "/WP") (class "Default")
      (node (ref "R11") (pin "2") (pinfunction "2_2") (pintype "passive"))
      (node (ref "U1") (pin "32") (pinfunction "PA11_32") (pintype "bidirectional"))
    )
    (net (code "32") (name "3Vref") (class "Default")
      (node (ref "3V") (pin "TP") (pinfunction "TP_TP") (pintype "input"))
      (node (ref "C11") (pin "2") (pinfunction "2_2") (pintype "passive"))
      (node (ref "C12") (pin "2") (pinfunction "2_2") (pintype "passive"))
      (node (ref "C13") (pin "2") (pinfunction "2_2") (pintype "passive"))
      (node (ref "C3") (pin "1") (pinfunction "1_1") (pintype "passive"))
      (node (ref "R3") (pin "2") (pinfunction "2_2") (pintype "passive"))
      (node (ref "U1") (pin "9") (pinfunction "VDDA_9") (pintype "power_in"))
      (node (ref "U3") (pin "6") (pinfunction "VOUT_6") (pintype "output"))
    )
    (net (code "33") (name "GND") (class "Default")
      (node (ref "C17") (pin "2") (pinfunction "2_2") (pintype "passive"))
      (node (ref "C6") (pin "2") (pinfunction "2_2") (pintype "passive"))
      (node (ref "GND_EXT") (pin "TP") (pinfunction "TP_TP") (pintype "input"))
      (node (ref "IC2") (pin "4") (pinfunction "GND_4") (pintype "bidirectional"))
      (node (ref "JP1") (pin "17") (pinfunction "17_17") (pintype "passive"))
      (node (ref "JP1") (pin "18") (pinfunction "18_18") (pintype "passive"))
      (node (ref "JP1") (pin "19") (pinfunction "19_19") (pintype "passive"))
      (node (ref "JP1") (pin "20") (pinfunction "20_20") (pintype "passive"))
      (node (ref "U4") (pin "2") (pinfunction "+VIN_2") (pintype "input"))
    )
    (net (code "34") (name "GND_galv") (class "Default")
      (node (ref "C1") (pin "2") (pinfunction "2_2") (pintype "passive"))
      (node (ref "C10") (pin "2") (pinfunction "2_2") (pintype "passive"))
      (node (ref "C11") (pin "1") (pinfunction "1_1") (pintype "passive"))
      (node (ref "C12") (pin "1") (pinfunction "1_1") (pintype "passive"))
      (node (ref "C13") (pin "1") (pinfunction "1_1") (pintype "passive"))
      (node (ref "C14") (pin "2") (pinfunction "2_2") (pintype "passive"))
      (node (ref "C15") (pin "2") (pinfunction "2_2") (pintype "passive"))
      (node (ref "C16") (pin "2") (pinfunction "2_2") (pintype "passive"))
      (node (ref "C18") (pin "2") (pinfunction "2_2") (pintype "passive"))
      (node (ref "C19") (pin "1") (pinfunction "1_1") (pintype "passive"))
      (node (ref "C2") (pin "2") (pinfunction "2_2") (pintype "passive"))
      (node (ref "C20") (pin "2") (pinfunction "2_2") (pintype "passive"))
      (node (ref "C21") (pin "2") (pinfunction "2_2") (pintype "passive"))
      (node (ref "C22") (pin "2") (pinfunction "2_2") (pintype "passive"))
      (node (ref "C23") (pin "2") (pinfunction "2_2") (pintype "passive"))
      (node (ref "C24") (pin "2") (pinfunction "2_2") (pintype "passive"))
      (node (ref "C25") (pin "2") (pinfunction "2_2") (pintype "passive"))
      (node (ref "C3") (pin "2") (pinfunction "2_2") (pintype "passive"))
      (node (ref "C4") (pin "2") (pinfunction "2_2") (pintype "passive"))
      (node (ref "C5") (pin "2") (pinfunction "2_2") (pintype "passive"))
      (node (ref "C7") (pin "2") (pinfunction "2_2") (pintype "passive"))
      (node (ref "C8") (pin "2") (pinfunction "2_2") (pintype "passive"))
      (node (ref "C9") (pin "2") (pinfunction "2_2") (pintype "passive"))
      (node (ref "GND_INT") (pin "TP") (pinfunction "TP_TP") (pintype "input"))
      (node (ref "I/O4") (pin "MP") (pinfunction "MP_MP") (pintype "passive"))
      (node (ref "IC1") (pin "4") (pinfunction "V-_4") (pintype "power_in"))
      (node (ref "JP2") (pin "5") (pinfunction "5_5") (pintype "passive"))
      (node (ref "LED1") (pin "K") (pinfunction "C_K") (pintype "passive"))
      (node (ref "R19") (pin "2") (pinfunction "2_2") (pintype "passive"))
      (node (ref "R20") (pin "2") (pinfunction "2_2") (pintype "passive"))
      (node (ref "R4") (pin "1") (pinfunction "1_1") (pintype "passive"))
      (node (ref "R6") (pin "1") (pinfunction "1_1") (pintype "passive"))
      (node (ref "U1") (pin "24") (pinfunction "VDD_2_24") (pintype "power_in"))
      (node (ref "U1") (pin "35") (pinfunction "VSS_3_35") (pintype "power_in"))
      (node (ref "U1") (pin "47") (pinfunction "VSS_47") (pintype "power_in"))
      (node (ref "U1") (pin "8") (pinfunction "VSSA_8") (pintype "power_in"))
      (node (ref "U2") (pin "2") (pinfunction "GND_2") (pintype "power_in"))
      (node (ref "U3") (pin "4") (pinfunction "GND_4") (pintype "power_in"))
      (node (ref "U4") (pin "3") (pinfunction "-VOUT_3") (pintype "output"))
      (node (ref "U5") (pin "4") (pinfunction "V-_4") (pintype "power_in"))
      (node (ref "U6") (pin "4") (pinfunction "GND_4") (pintype "power_in"))
      (node (ref "U7") (pin "4") (pinfunction "GND_4") (pintype "passive"))
      (node (ref "U8") (pin "16") (pinfunction "GND_16") (pintype "passive"))
      (node (ref "U8") (pin "9") (pinfunction "GND_2_9") (pintype "passive"))
      (node (ref "U9") (pin "2") (pinfunction "V-_2") (pintype "power_in"))
    )
    (net (code "35") (name "Net-(CR1-ADJ)") (class "Default")
      (node (ref "ADJ") (pin "TP") (pinfunction "TP_TP") (pintype "passive"))
      (node (ref "CR1") (pin "1") (pinfunction "ADJ_1") (pintype "passive"))
      (node (ref "R7") (pin "2") (pinfunction "2_2") (pintype "passive"))
      (node (ref "R8") (pin "2") (pinfunction "2_2") (pintype "passive"))
    )
    (net (code "36") (name "Net-(CR1-V-)") (class "Default")
      (node (ref "CR1") (pin "6") (pinfunction "V-_6") (pintype "power_in"))
      (node (ref "D1") (pin "2") (pinfunction "A_2") (pintype "passive"))
      (node (ref "R24") (pin "2") (pinfunction "2_2") (pintype "passive"))
      (node (ref "R7") (pin "1") (pinfunction "1_1") (pintype "passive"))
      (node (ref "V-") (pin "TP") (pinfunction "TP_TP") (pintype "passive"))
    )
    (net (code "37") (name "Net-(IC1B-+IN)") (class "Default")
      (node (ref "IC1") (pin "5") (pinfunction "+IN_5") (pintype "input"))
      (node (ref "R3") (pin "1") (pinfunction "1_1") (pintype "passive"))
      (node (ref "R4") (pin "2") (pinfunction "2_2") (pintype "passive"))
    )
    (net (code "38") (name "Net-(IC1B--IN)") (class "Default")
      (node (ref "IC1") (pin "6") (pinfunction "-IN_6") (pintype "input"))
      (node (ref "IC1") (pin "7") (pinfunction "OUT_7") (pintype "output"))
      (node (ref "REF") (pin "TP") (pinfunction "TP_TP") (pintype "passive"))
      (node (ref "U5") (pin "5") (pinfunction "REF_5") (pintype "input"))
    )
    (net (code "39") (name "Net-(IC2-ANODE)") (class "Default")
      (node (ref "IC2") (pin "1") (pinfunction "ANODE_1") (pintype "bidirectional"))
      (node (ref "R17") (pin "1") (pinfunction "1_1") (pintype "passive"))
    )
    (net (code "40") (name "Net-(LED1-PadA)") (class "Default")
      (node (ref "LED1") (pin "A") (pinfunction "A_A") (pintype "passive"))
      (node (ref "R9") (pin "1") (pinfunction "1_1") (pintype "passive"))
    )
    (net (code "41") (name "Net-(U3-TRIM{slash}NR)") (class "Default")
      (node (ref "C4") (pin "1") (pinfunction "1_1") (pintype "passive"))
      (node (ref "U3") (pin "5") (pinfunction "TRIM/NR_5") (pintype "passive"))
    )
    (net (code "42") (name "Net-(U5-IN-)") (class "Default")
      (node (ref "R1") (pin "1") (pinfunction "1_1") (pintype "passive"))
      (node (ref "R18") (pin "1") (pinfunction "1_1") (pintype "passive"))
      (node (ref "R2") (pin "2") (pinfunction "2_2") (pintype "passive"))
      (node (ref "U5") (pin "2") (pinfunction "IN-_2") (pintype "input"))
      (node (ref "UIN") (pin "TP") (pinfunction "TP_TP") (pintype "passive"))
    )
    (net (code "43") (name "Net-(U5-OUT)") (class "Default")
      (node (ref "R5") (pin "2") (pinfunction "2_2") (pintype "passive"))
      (node (ref "TP11") (pin "TP") (pinfunction "TP_TP") (pintype "passive"))
      (node (ref "U5") (pin "6") (pinfunction "OUT_6") (pintype "output"))
    )
    (net (code "44") (name "Net-(U6-IN-)") (class "Default")
      (node (ref "I/O5") (pin "MP") (pinfunction "MP_MP") (pintype "passive"))
      (node (ref "R20") (pin "1") (pinfunction "1_1") (pintype "passive"))
      (node (ref "U6") (pin "2") (pinfunction "IN-_2") (pintype "input"))
      (node (ref "U6") (pin "6") (pinfunction "OUT_6") (pintype "output"))
    )
    (net (code "45") (name "Net-(U7-CLK)") (class "Default")
      (node (ref "R13") (pin "2") (pinfunction "2_2") (pintype "passive"))
      (node (ref "SCK2") (pin "TP") (pinfunction "TP_TP") (pintype "passive"))
      (node (ref "U7") (pin "6") (pinfunction "CLK_6") (pintype "passive"))
    )
    (net (code "46") (name "Net-(U7-DI(IO0))") (class "Default")
      (node (ref "MOSI2") (pin "TP") (pinfunction "TP_TP") (pintype "passive"))
      (node (ref "R14") (pin "2") (pinfunction "2_2") (pintype "passive"))
      (node (ref "U7") (pin "5") (pinfunction "DI(IO0)_5") (pintype "passive"))
    )
    (net (code "47") (name "Net-(U7-DO(IO1))") (class "Default")
      (node (ref "R10") (pin "1") (pinfunction "1_1") (pintype "passive"))
      (node (ref "U7") (pin "2") (pinfunction "DO(IO1)_2") (pintype "passive"))
    )
    (net (code "48") (name "Net-(U7-{slash}CS)") (class "Default")
      (node (ref "R15") (pin "1") (pinfunction "1_1") (pintype "passive"))
      (node (ref "U7") (pin "1") (pinfunction "/CS_1") (pintype "passive"))
    )
    (net (code "49") (name "Net-(U7-{slash}HOLD_OR_{slash}RESET(IO3))") (class "Default")
      (node (ref "R12") (pin "2") (pinfunction "2_2") (pintype "passive"))
      (node (ref "U7") (pin "7") (pinfunction "/HOLD_OR_/RESET(IO3)_7") (pintype "passive"))
    )
    (net (code "50") (name "Net-(U7-{slash}WP(IO2))") (class "Default")
      (node (ref "R11") (pin "1") (pinfunction "1_1") (pintype "passive"))
      (node (ref "U7") (pin "3") (pinfunction "/WP(IO2)_3") (pintype "passive"))
    )
    (net (code "51") (name "Net-(U8-ANODE1)") (class "Default")
      (node (ref "R21") (pin "1") (pinfunction "1_1") (pintype "passive"))
      (node (ref "U8") (pin "1") (pinfunction "ANODE1_1") (pintype "bidirectional"))
    )
    (net (code "52") (name "Net-(U8-ANODE2)") (class "Default")
      (node (ref "R21") (pin "2") (pinfunction "2_2") (pintype "passive"))
      (node (ref "U8") (pin "3") (pinfunction "ANODE2_3") (pintype "bidirectional"))
    )
    (net (code "53") (name "Net-(U8-ANODE3)") (class "Default")
      (node (ref "R21") (pin "3") (pinfunction "3_3") (pintype "passive"))
      (node (ref "U8") (pin "5") (pinfunction "ANODE3_5") (pintype "bidirectional"))
    )
    (net (code "54") (name "Net-(U8-ANODE4)") (class "Default")
      (node (ref "R21") (pin "4") (pinfunction "4_4") (pintype "passive"))
      (node (ref "U8") (pin "7") (pinfunction "ANODE4_7") (pintype "bidirectional"))
    )
    (net (code "55") (name "unconnected-(CR1-NC-Pad8)") (class "Default")
      (node (ref "CR1") (pin "8") (pinfunction "NC_8") (pintype "no_connect"))
    )
    (net (code "56") (name "unconnected-(CR1-NC_2-Pad2)") (class "Default")
      (node (ref "CR1") (pin "2") (pinfunction "NC_2_2") (pintype "no_connect"))
    )
    (net (code "57") (name "unconnected-(CR1-NC_3-Pad3)") (class "Default")
      (node (ref "CR1") (pin "3") (pinfunction "NC_3_3") (pintype "no_connect"))
    )
    (net (code "58") (name "unconnected-(CR1-NC_4-Pad5)") (class "Default")
      (node (ref "CR1") (pin "5") (pinfunction "NC_4_5") (pintype "no_connect"))
    )
    (net (code "59") (name "unconnected-(CR1-NC_5-Pad7)") (class "Default")
      (node (ref "CR1") (pin "7") (pinfunction "NC_5_7") (pintype "no_connect"))
    )
    (net (code "60") (name "unconnected-(IC2-N.C.-Pad2)") (class "Default")
      (node (ref "IC2") (pin "2") (pinfunction "N.C._2") (pintype "no_connect"))
    )
    (net (code "61") (name "unconnected-(JP1-Pad15)") (class "Default")
      (node (ref "JP1") (pin "15") (pinfunction "15_15") (pintype "passive"))
    )
    (net (code "62") (name "unconnected-(JP1-Pad16)") (class "Default")
      (node (ref "JP1") (pin "16") (pinfunction "16_16") (pintype "passive"))
    )
    (net (code "63") (name "unconnected-(U1-PA1-Pad11)") (class "Default")
      (node (ref "U1") (pin "11") (pinfunction "PA1_11") (pintype "bidirectional"))
    )
    (net (code "64") (name "unconnected-(U1-PA3-Pad13)") (class "Default")
      (node (ref "U1") (pin "13") (pinfunction "PA3_13") (pintype "bidirectional"))
    )
    (net (code "65") (name "unconnected-(U1-PA8-Pad29)") (class "Default")
      (node (ref "U1") (pin "29") (pinfunction "PA8_29") (pintype "bidirectional"))
    )
    (net (code "66") (name "unconnected-(U1-PA10-Pad31)") (class "Default")
      (node (ref "U1") (pin "31") (pinfunction "PA10_31") (pintype "bidirectional"))
    )
    (net (code "67") (name "unconnected-(U1-PA12-Pad33)") (class "Default")
      (node (ref "U1") (pin "33") (pinfunction "PA12_33") (pintype "bidirectional"))
    )
    (net (code "68") (name "unconnected-(U1-PA15-Pad38)") (class "Default")
      (node (ref "U1") (pin "38") (pinfunction "PA15_38") (pintype "bidirectional"))
    )
    (net (code "69") (name "unconnected-(U1-PB1-Pad19)") (class "Default")
      (node (ref "U1") (pin "19") (pinfunction "PB1_19") (pintype "bidirectional"))
    )
    (net (code "70") (name "unconnected-(U1-PB2-Pad20)") (class "Default")
      (node (ref "U1") (pin "20") (pinfunction "PB2_20") (pintype "bidirectional"))
    )
    (net (code "71") (name "unconnected-(U1-PB3-Pad39)") (class "Default")
      (node (ref "U1") (pin "39") (pinfunction "PB3_39") (pintype "bidirectional"))
    )
    (net (code "72") (name "unconnected-(U1-PB4-Pad40)") (class "Default")
      (node (ref "U1") (pin "40") (pinfunction "PB4_40") (pintype "bidirectional"))
    )
    (net (code "73") (name "unconnected-(U1-PB6-Pad42)") (class "Default")
      (node (ref "U1") (pin "42") (pinfunction "PB6_42") (pintype "bidirectional"))
    )
    (net (code "74") (name "unconnected-(U1-PB7-Pad43)") (class "Default")
      (node (ref "U1") (pin "43") (pinfunction "PB7_43") (pintype "bidirectional"))
    )
    (net (code "75") (name "unconnected-(U1-PB8-Pad45)") (class "Default")
      (node (ref "U1") (pin "45") (pinfunction "PB8_45") (pintype "bidirectional"))
    )
    (net (code "76") (name "unconnected-(U1-PB9-Pad46)") (class "Default")
      (node (ref "U1") (pin "46") (pinfunction "PB9_46") (pintype "bidirectional"))
    )
    (net (code "77") (name "unconnected-(U1-PB10-Pad21)") (class "Default")
      (node (ref "U1") (pin "21") (pinfunction "PB10_21") (pintype "bidirectional"))
    )
    (net (code "78") (name "unconnected-(U1-PC13-Pad2)") (class "Default")
      (node (ref "U1") (pin "2") (pinfunction "PC13_2") (pintype "bidirectional"))
    )
    (net (code "79") (name "unconnected-(U1-PC14{slash}OSC32_IN-Pad3)") (class "Default")
      (node (ref "U1") (pin "3") (pinfunction "PC14/OSC32_IN_3") (pintype "bidirectional"))
    )
    (net (code "80") (name "unconnected-(U1-PC15{slash}OSC32_OUT-Pad4)") (class "Default")
      (node (ref "U1") (pin "4") (pinfunction "PC15/OSC32_OUT_4") (pintype "bidirectional"))
    )
    (net (code "81") (name "unconnected-(U1-PH0{slash}OSC_IN-Pad5)") (class "Default")
      (node (ref "U1") (pin "5") (pinfunction "PH0/OSC_IN_5") (pintype "bidirectional"))
    )
    (net (code "82") (name "unconnected-(U1-PH1{slash}OSC_OUT-Pad6)") (class "Default")
      (node (ref "U1") (pin "6") (pinfunction "PH1/OSC_OUT_6") (pintype "bidirectional"))
    )
    (net (code "83") (name "unconnected-(U1-PH3{slash}BOOT0-Pad44)") (class "Default")
      (node (ref "U1") (pin "44") (pinfunction "PH3/BOOT0_44") (pintype "bidirectional"))
    )
    (net (code "84") (name "unconnected-(U2-N{slash}C-Pad4)") (class "Default")
      (node (ref "U2") (pin "4") (pinfunction "N/C_4") (pintype "no_connect"))
    )
    (net (code "85") (name "unconnected-(U3-DNC-Pad8)") (class "Default")
      (node (ref "U3") (pin "8") (pinfunction "DNC_8") (pintype "passive"))
    )
    (net (code "86") (name "unconnected-(U3-DNC_2-Pad1)") (class "Default")
      (node (ref "U3") (pin "1") (pinfunction "DNC_2_1") (pintype "passive"))
    )
    (net (code "87") (name "unconnected-(U3-NC-Pad7)") (class "Default")
      (node (ref "U3") (pin "7") (pinfunction "NC_7") (pintype "no_connect"))
    )
    (net (code "88") (name "unconnected-(U3-TEMP-Pad3)") (class "Default")
      (node (ref "U3") (pin "3") (pinfunction "TEMP_3") (pintype "passive"))
    )
    (net (code "89") (name "unconnected-(U5-RG-Pad8)") (class "Default")
      (node (ref "U5") (pin "8") (pinfunction "RG_8") (pintype "passive"))
    )
    (net (code "90") (name "unconnected-(U5-RG_2-Pad1)") (class "Default")
      (node (ref "U5") (pin "1") (pinfunction "RG_2_1") (pintype "passive"))
    )
    (net (code "91") (name "unconnected-(U6-NC-Pad5)") (class "Default")
      (node (ref "U6") (pin "5") (pinfunction "NC_5") (pintype "passive"))
    )
    (net (code "92") (name "unconnected-(U6-NC_2-Pad1)") (class "Default")
      (node (ref "U6") (pin "1") (pinfunction "NC_2_1") (pintype "passive"))
    )
    (net (code "93") (name "unconnected-(U6-PadEPAD)") (class "Default")
      (node (ref "U6") (pin "EPAD") (pinfunction "EPAD_EPAD") (pintype "passive"))
    )
  )
)
